# ReuseBlock_SinglePhaseDriver_BLDCV4_2024.net
KiCad netlist of a schematic drawn in EasyEDA Pro
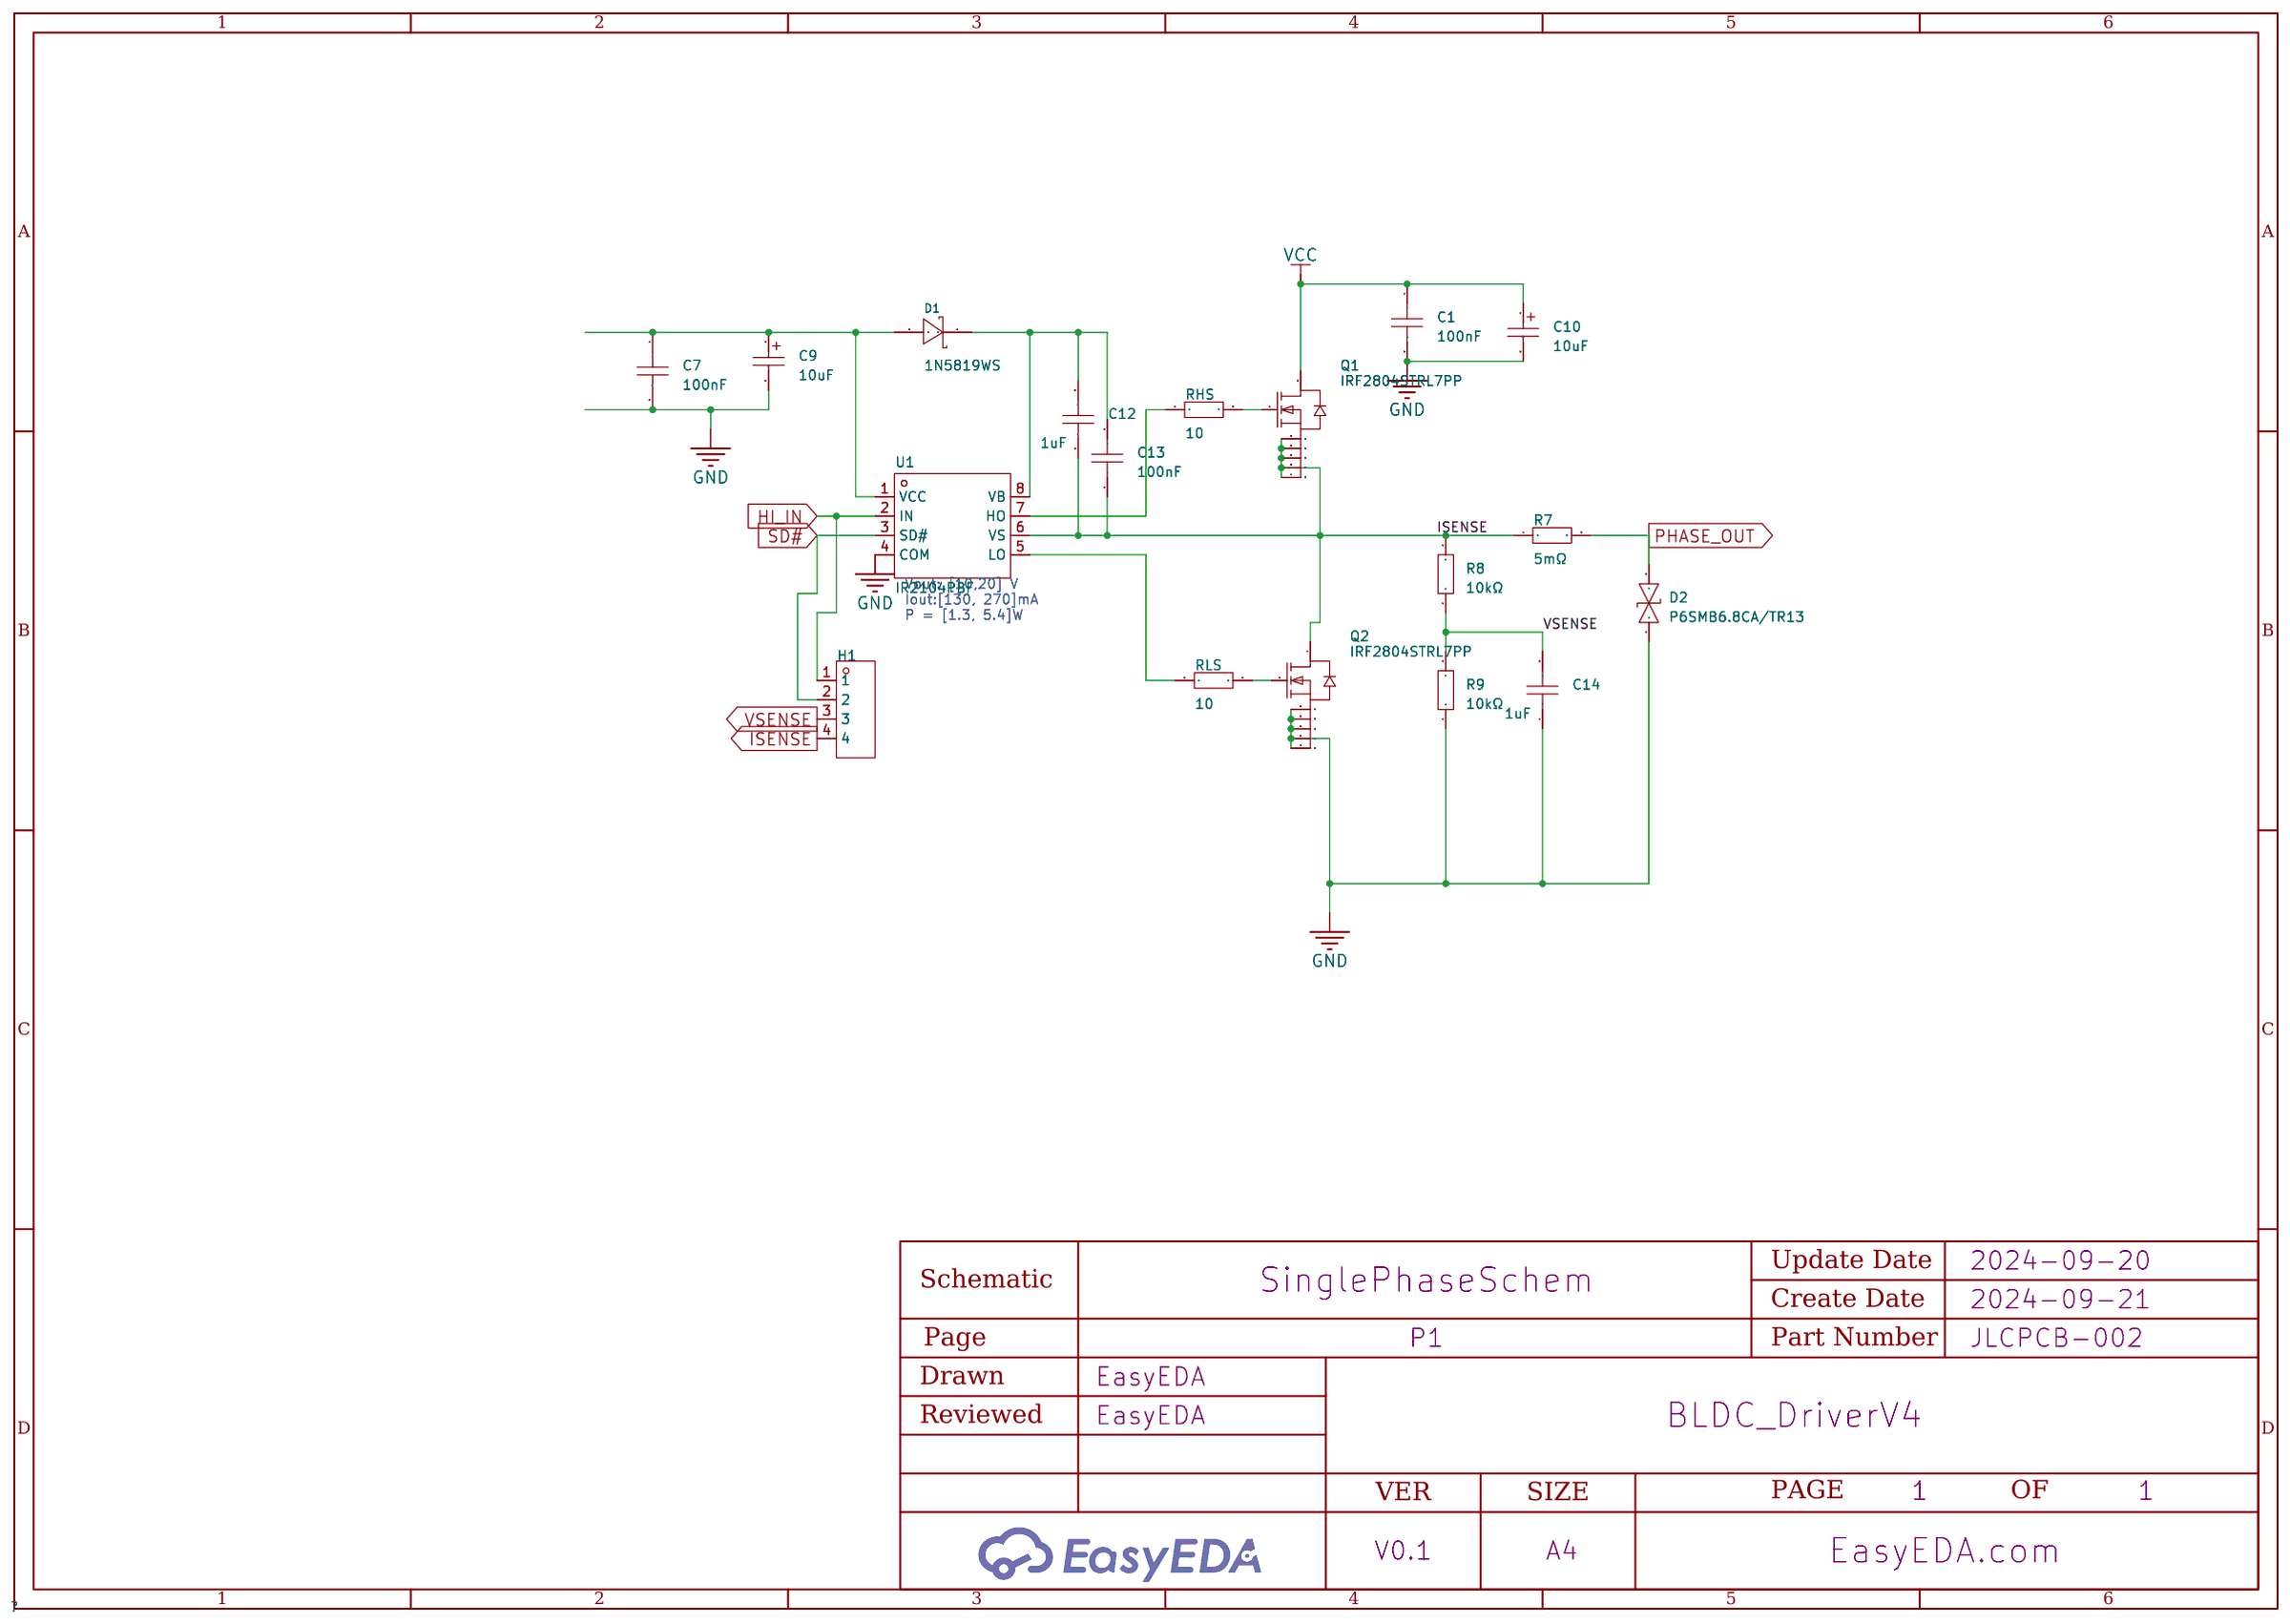
[diagram p0: schematic sheet]

(export (version "E")
  (design (tool "Eeschema 10.0.6"))
  (components
    (comp (ref "C1")
      (value "100nF")
      (footprint "easyedapro:C0603")
      (libsource (lib "easyedapro") (part "CAP"))
    )
    (comp (ref "C7")
      (value "100nF")
      (footprint "easyedapro:C0603")
      (libsource (lib "easyedapro") (part "CAP"))
    )
    (comp (ref "C9")
      (value "10uF")
      (footprint "easyedapro:CAP-SMD_BD5.0-L5.3-W5.3-LS6.3-FD")
      (libsource (lib "easyedapro") (part "C_Ele_SMD"))
    )
    (comp (ref "C10")
      (value "10uF")
      (footprint "easyedapro:CAP-SMD_BD5.0-L5.3-W5.3-LS6.3-FD")
      (libsource (lib "easyedapro") (part "C_Ele_SMD"))
    )
    (comp (ref "C12")
      (value "1uF")
      (footprint "easyedapro:CAP-TH_L7.2-W2.5-P5.00-D0.6")
      (fields (field (name "Manufacturer Part") "SMEC334J100M2") (field (name "Manufacturer") "CHAMPION(全鹏)"))
      (libsource (lib "easyedapro") (part "SMEC334J100M2"))
    )
    (comp (ref "C13")
      (value "100nF")
      (footprint "easyedapro:C0603")
      (libsource (lib "easyedapro") (part "CAP"))
    )
    (comp (ref "C14")
      (value "1uF")
      (footprint "easyedapro:CAP-TH_L7.2-W2.5-P5.00-D0.6")
      (fields (field (name "Manufacturer Part") "SMEC334J100M2") (field (name "Manufacturer") "CHAMPION(全鹏)"))
      (libsource (lib "easyedapro") (part "SMEC334J100M2"))
    )
    (comp (ref "D1")
      (value "1N5819WS")
      (footprint "easyedapro:SOD-323_L1.8-W1.3-LS2.5-RD")
      (description "Forward Voltage (Vf@If):600mV@1A Reverse Voltage (Vr):40V Average Rectified Current (Io):1A")
      (fields (field (name "Manufacturer") "Hottech(合科泰)"))
      (libsource (lib "easyedapro") (part "1N5819WS"))
    )
    (comp (ref "D2")
      (value "P6SMB6.8CA/TR13")
      (footprint "easyedapro:SMB_L4.6-W3.6-LS5.3-BI")
      (fields (field (name "Manufacturer") "Brightking(君耀电子)"))
      (libsource (lib "easyedapro") (part "P6SMB6.8CA-C78395"))
    )
    (comp (ref "H1")
      (value "~")
      (footprint "easyedapro:HDR-TH_4P-P2.54-V-M")
      (libsource (lib "easyedapro") (part "PZ254V-11-04P"))
    )
    (comp (ref "Q1")
      (value "IRF2804STRL7PP")
      (footprint "easyedapro:D2PAK-7_L10.6-W9.6-P1.27-LS15.9-BR")
      (fields (field (name "Manufacturer") "Infineon(英飞凌)"))
      (libsource (lib "easyedapro") (part "IRF2804STRL7PP"))
    )
    (comp (ref "Q2")
      (value "IRF2804STRL7PP")
      (footprint "easyedapro:D2PAK-7_L10.6-W9.6-P1.27-LS15.9-BR")
      (fields (field (name "Manufacturer") "Infineon(英飞凌)"))
      (libsource (lib "easyedapro") (part "IRF2804STRL7PP"))
    )
    (comp (ref "R7")
      (value "5mΩ")
      (footprint "easyedapro:R2512")
      (fields
        (field (name "Manufacturer Part") "PA2512FKF7W0R005E")
        (field (name "Manufacturer") "YAGEO(国巨)")
      )
      (libsource (lib "easyedapro") (part "PA2512FKF7W0R005L"))
    )
    (comp (ref "R8")
      (value "10kΩ")
      (footprint "easyedapro:RES-TH_BD3.3-L9.0-P13.00-D0.6")
      (libsource (lib "easyedapro") (part "Res"))
    )
    (comp (ref "R9")
      (value "10kΩ")
      (footprint "easyedapro:RES-TH_BD3.3-L9.0-P13.00-D0.6")
      (libsource (lib "easyedapro") (part "Res"))
    )
    (comp (ref "RHS")
      (value "10")
      (footprint "easyedapro:RES-TH_BD3.3-L9.0-P13.00-D0.6")
      (libsource (lib "easyedapro") (part "Res"))
    )
    (comp (ref "RLS")
      (value "10")
      (footprint "easyedapro:RES-TH_BD3.3-L9.0-P13.00-D0.6")
      (libsource (lib "easyedapro") (part "Res"))
    )
    (comp (ref "U1")
      (value "IR2104PBF")
      (footprint "easyedapro:DIP-8_L9.9-W6.6-P2.54-LS7.62-BL")
      (fields (field (name "Manufacturer") "Infineon(英飞凌)"))
      (libsource (lib "easyedapro") (part "IR2104PBF"))
    )
  )
  (nets
    (net (code "1") (name "GND") (class "Default")
      (node (ref "C1") (pin "2") (pinfunction "2_2") (pintype "input"))
      (node (ref "C10") (pin "2") (pinfunction "2_2") (pintype "input"))
      (node (ref "C14") (pin "1") (pinfunction "1_1") (pintype "input"))
      (node (ref "C7") (pin "2") (pinfunction "2_2") (pintype "input"))
      (node (ref "C9") (pin "2") (pinfunction "2_2") (pintype "input"))
      (node (ref "D2") (pin "1") (pinfunction "1_1") (pintype "unspecified"))
      (node (ref "Q2") (pin "2") (pinfunction "S_2") (pintype "unspecified"))
      (node (ref "Q2") (pin "3") (pinfunction "S_3") (pintype "unspecified"))
      (node (ref "Q2") (pin "5") (pinfunction "S_5") (pintype "unspecified"))
      (node (ref "Q2") (pin "6") (pinfunction "S_6") (pintype "unspecified"))
      (node (ref "Q2") (pin "7") (pinfunction "S_7") (pintype "unspecified"))
      (node (ref "R9") (pin "1") (pinfunction "1_1") (pintype "input"))
      (node (ref "U1") (pin "4") (pinfunction "COM_4") (pintype "unspecified"))
    )
    (net (code "2") (name "HI_IN") (class "Default")
      (node (ref "H1") (pin "1") (pinfunction "1_1") (pintype "unspecified"))
      (node (ref "U1") (pin "2") (pinfunction "IN_2") (pintype "unspecified"))
    )
    (net (code "3") (name "ISENSE") (class "Default")
      (node (ref "C12") (pin "1") (pinfunction "1_1") (pintype "input"))
      (node (ref "C13") (pin "2") (pinfunction "2_2") (pintype "input"))
      (node (ref "H1") (pin "4") (pinfunction "4_4") (pintype "unspecified"))
      (node (ref "Q1") (pin "2") (pinfunction "S_2") (pintype "unspecified"))
      (node (ref "Q1") (pin "3") (pinfunction "S_3") (pintype "unspecified"))
      (node (ref "Q1") (pin "5") (pinfunction "S_5") (pintype "unspecified"))
      (node (ref "Q1") (pin "6") (pinfunction "S_6") (pintype "unspecified"))
      (node (ref "Q1") (pin "7") (pinfunction "S_7") (pintype "unspecified"))
      (node (ref "Q2") (pin "4") (pinfunction "D_4") (pintype "unspecified"))
      (node (ref "R7") (pin "1") (pinfunction "1_1") (pintype "unspecified"))
      (node (ref "R8") (pin "2") (pinfunction "2_2") (pintype "input"))
      (node (ref "U1") (pin "6") (pinfunction "VS_6") (pintype "unspecified"))
    )
    (net (code "4") (name "Net-(D1-A)") (class "Default")
      (node (ref "C7") (pin "1") (pinfunction "1_1") (pintype "input"))
      (node (ref "C9") (pin "1") (pinfunction "1_1") (pintype "input"))
      (node (ref "D1") (pin "2") (pinfunction "A_2") (pintype "input"))
      (node (ref "U1") (pin "1") (pinfunction "VCC_1") (pintype "unspecified"))
    )
    (net (code "5") (name "Net-(D1-K)") (class "Default")
      (node (ref "C12") (pin "2") (pinfunction "2_2") (pintype "input"))
      (node (ref "C13") (pin "1") (pinfunction "1_1") (pintype "input"))
      (node (ref "D1") (pin "1") (pinfunction "K_1") (pintype "input"))
      (node (ref "U1") (pin "8") (pinfunction "VB_8") (pintype "unspecified"))
    )
    (net (code "6") (name "Net-(Q1-G)") (class "Default")
      (node (ref "Q1") (pin "1") (pinfunction "G_1") (pintype "unspecified"))
      (node (ref "RHS") (pin "2") (pinfunction "2_2") (pintype "input"))
    )
    (net (code "7") (name "Net-(Q2-G)") (class "Default")
      (node (ref "Q2") (pin "1") (pinfunction "G_1") (pintype "unspecified"))
      (node (ref "RLS") (pin "2") (pinfunction "2_2") (pintype "input"))
    )
    (net (code "8") (name "Net-(U1-HO)") (class "Default")
      (node (ref "RHS") (pin "1") (pinfunction "1_1") (pintype "input"))
      (node (ref "U1") (pin "7") (pinfunction "HO_7") (pintype "unspecified"))
    )
    (net (code "9") (name "Net-(U1-LO)") (class "Default")
      (node (ref "RLS") (pin "1") (pinfunction "1_1") (pintype "input"))
      (node (ref "U1") (pin "5") (pinfunction "LO_5") (pintype "unspecified"))
    )
    (net (code "10") (name "PHASE_OUT") (class "Default")
      (node (ref "D2") (pin "2") (pinfunction "2_2") (pintype "unspecified"))
      (node (ref "R7") (pin "2") (pinfunction "2_2") (pintype "unspecified"))
    )
    (net (code "11") (name "SD#") (class "Default")
      (node (ref "H1") (pin "2") (pinfunction "2_2") (pintype "unspecified"))
      (node (ref "U1") (pin "3") (pinfunction "SD#_3") (pintype "unspecified"))
    )
    (net (code "12") (name "VCC") (class "Default")
      (node (ref "C1") (pin "1") (pinfunction "1_1") (pintype "input"))
      (node (ref "C10") (pin "1") (pinfunction "1_1") (pintype "input"))
      (node (ref "Q1") (pin "4") (pinfunction "D_4") (pintype "unspecified"))
    )
    (net (code "13") (name "VSENSE") (class "Default")
      (node (ref "C14") (pin "2") (pinfunction "2_2") (pintype "input"))
      (node (ref "H1") (pin "3") (pinfunction "3_3") (pintype "unspecified"))
      (node (ref "R8") (pin "1") (pinfunction "1_1") (pintype "input"))
      (node (ref "R9") (pin "2") (pinfunction "2_2") (pintype "input"))
    )
  )
)
